# CONNECTOR_B.net
KiCad netlist of a schematic drawn in Altium Designer
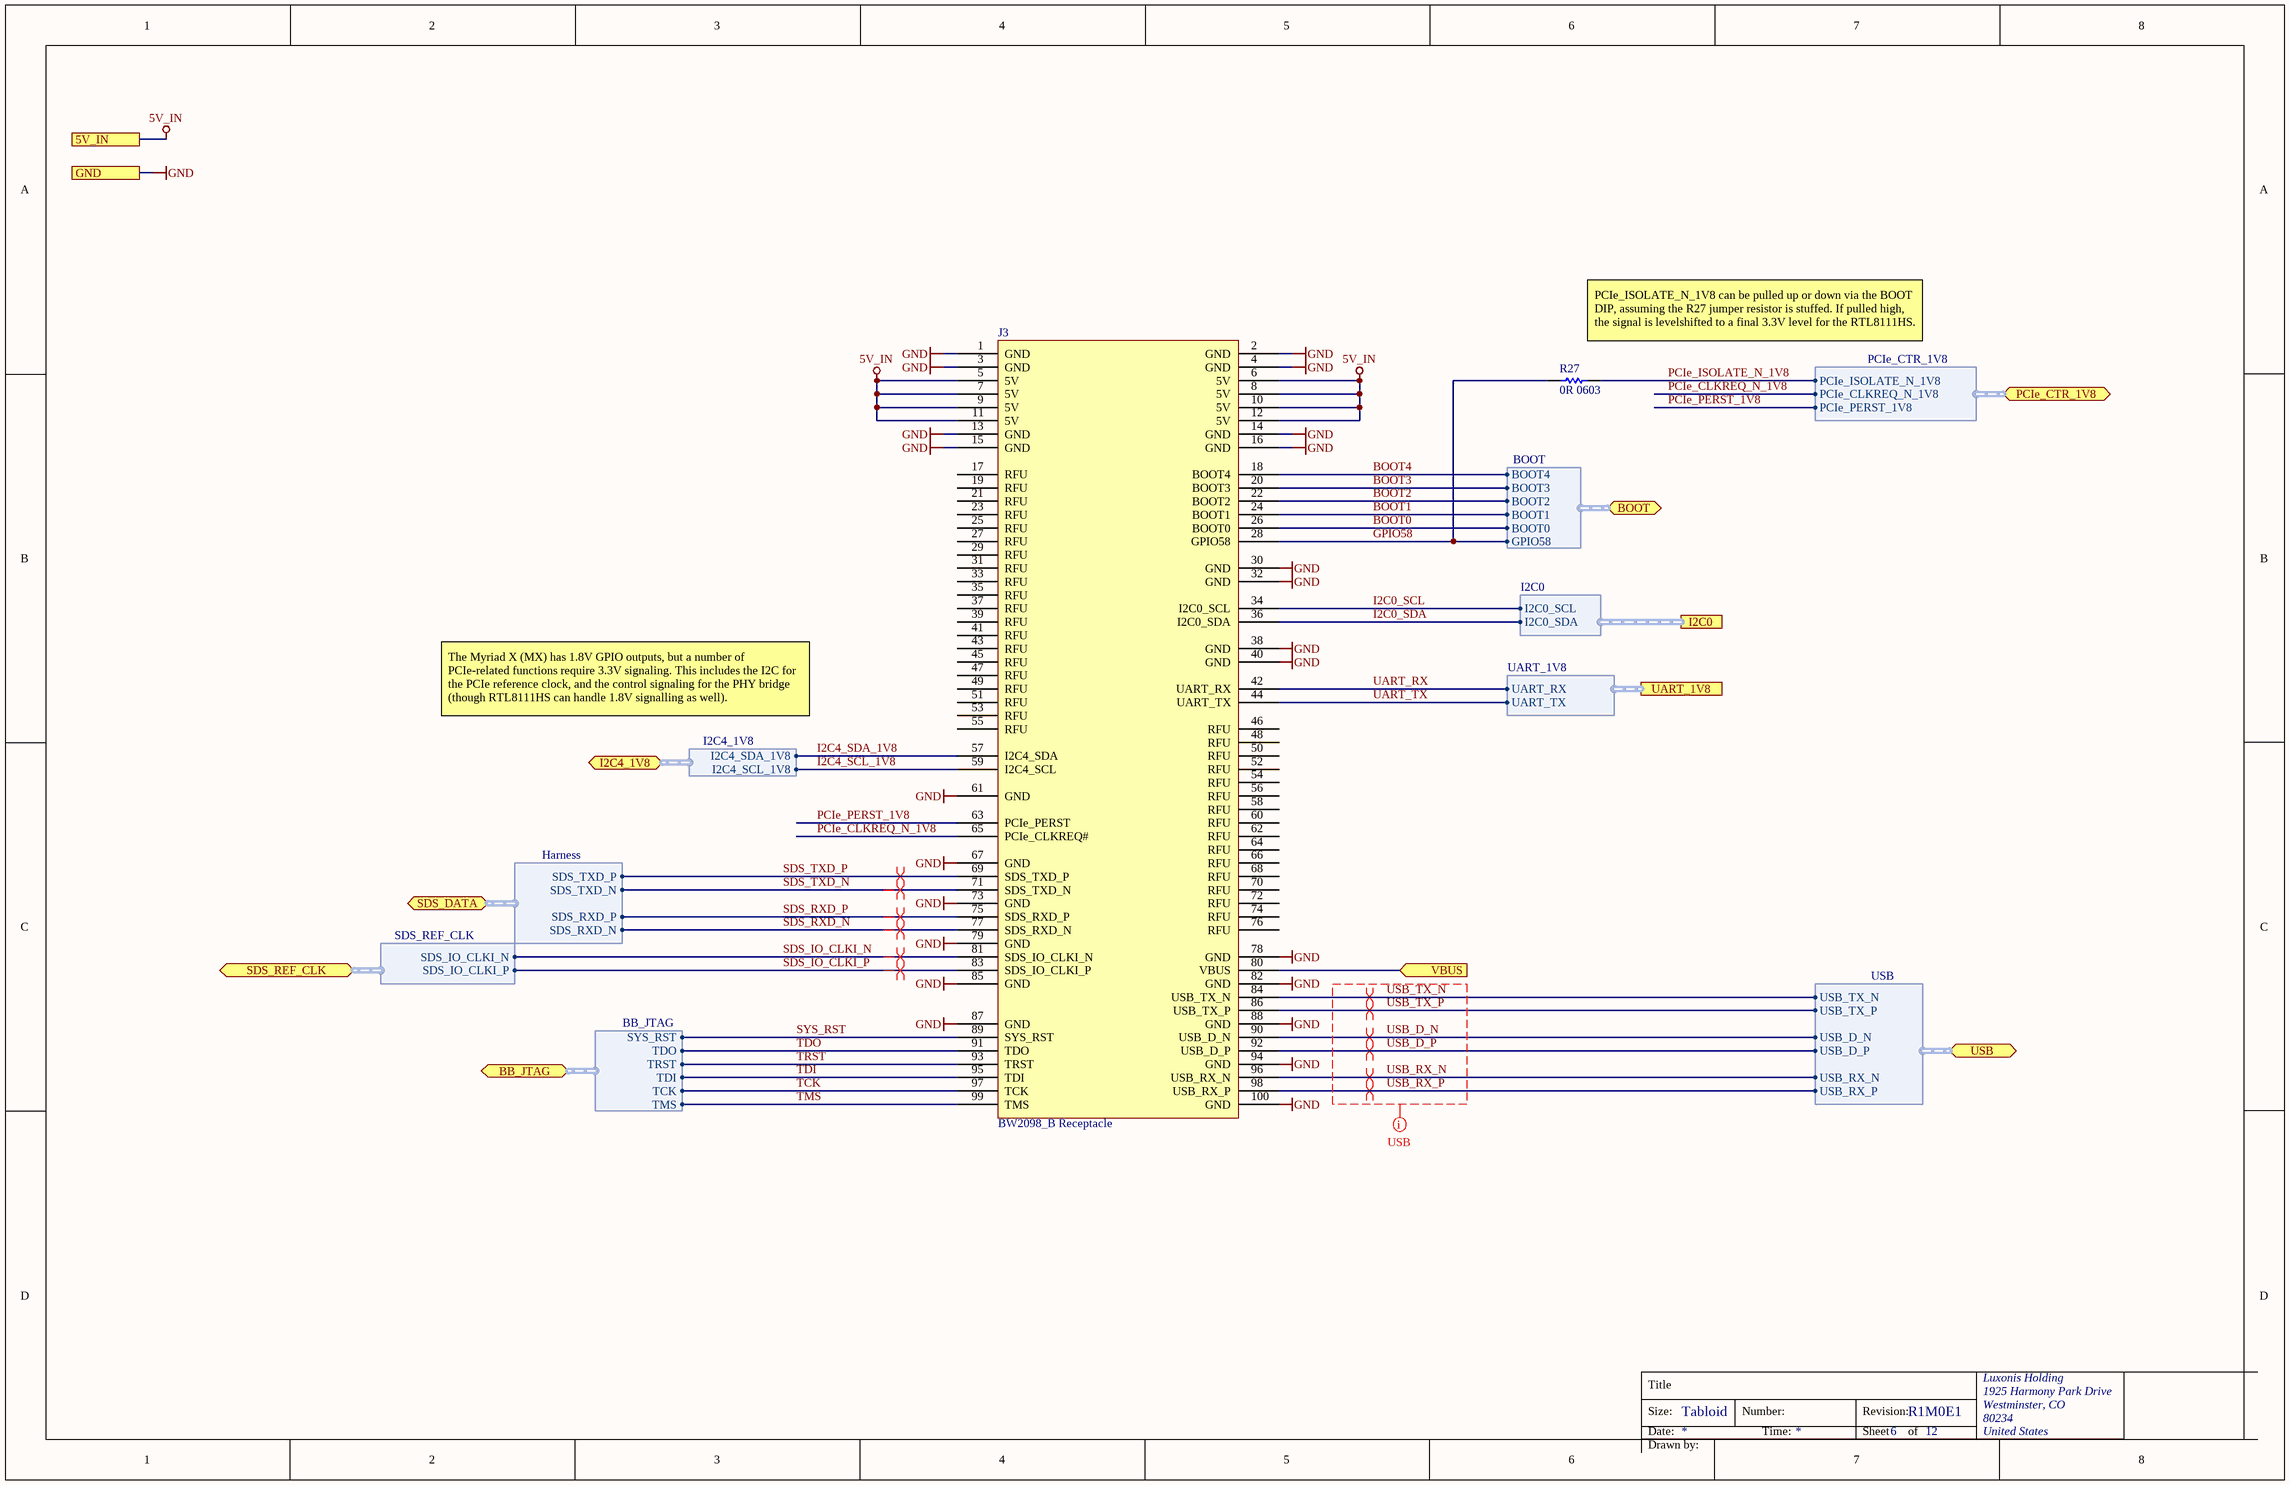
[diagram p0: CONNECTOR_B.SchDoc]

(export (version "E")
  (design (tool "Eeschema 10.0.6"))
  (components
    (comp (ref "J3")
      (value "BW2098_B Receptacle")
      (footprint "LuxonisMaster:DF40HC-3.0-100DS-0.4V_minpad")
      (description "CONN RCPT 100POS 0.4MM SMD GOLD BW2098_B Receptacle")
      (libsource (lib "BW2098POE") (part "DF40HC(3.0)-100DS-0.4V_BW2098_B"))
    )
    (comp (ref "R27")
      (value "0R 0603")
      (footprint "RES_Altium_Vault_Generic:RESC0603(1608)_N")
      (fields (field (name "TOLERANCE") "5%"))
      (libsource (lib "LuxonisMaster") (part "CRCW06030000Z0EA"))
    )
  )
  (nets
    (net (code "10") (name "/BOOT0") (class "Default")
      (node (ref "J3") (pin "26") (pinfunction "BOOT0_26") (pintype "passive"))
    )
    (net (code "11") (name "/BOOT1") (class "Default")
      (node (ref "J3") (pin "24") (pinfunction "BOOT1_24") (pintype "passive"))
    )
    (net (code "12") (name "/BOOT2") (class "Default")
      (node (ref "J3") (pin "22") (pinfunction "BOOT2_22") (pintype "passive"))
    )
    (net (code "13") (name "/BOOT3") (class "Default")
      (node (ref "J3") (pin "20") (pinfunction "BOOT3_20") (pintype "passive"))
    )
    (net (code "14") (name "/BOOT4") (class "Default")
      (node (ref "J3") (pin "18") (pinfunction "BOOT4_18") (pintype "passive"))
    )
    (net (code "15") (name "/GPIO58") (class "Default")
      (node (ref "J3") (pin "28") (pinfunction "GPIO58_28") (pintype "passive"))
      (node (ref "R27") (pin "1") (pinfunction "1_1") (pintype "passive"))
    )
    (net (code "16") (name "/I2C0_SCL") (class "Default")
      (node (ref "J3") (pin "34") (pinfunction "I2C0_SCL_34") (pintype "passive"))
    )
    (net (code "17") (name "/I2C0_SDA") (class "Default")
      (node (ref "J3") (pin "36") (pinfunction "I2C0_SDA_36") (pintype "passive"))
    )
    (net (code "18") (name "/I2C4_SCL_1V8") (class "Default")
      (node (ref "J3") (pin "59") (pinfunction "I2C4_SCL_59") (pintype "passive"))
    )
    (net (code "19") (name "/I2C4_SDA_1V8") (class "Default")
      (node (ref "J3") (pin "57") (pinfunction "I2C4_SDA_57") (pintype "passive"))
    )
    (net (code "20") (name "/PCIe_CLKREQ_N_1V8") (class "Default")
      (node (ref "J3") (pin "65") (pinfunction "PCIe_CLKREQ#_65") (pintype "passive"))
    )
    (net (code "21") (name "/PCIe_ISOLATE_N_1V8") (class "Default")
      (node (ref "R27") (pin "2") (pinfunction "2_2") (pintype "passive"))
    )
    (net (code "22") (name "/PCIe_PERST_1V8") (class "Default")
      (node (ref "J3") (pin "63") (pinfunction "PCIe_PERST_63") (pintype "passive"))
    )
    (net (code "23") (name "/SDS_IO_CLKI_N") (class "Default")
      (node (ref "J3") (pin "81") (pinfunction "SDS_IO_CLKI_N_81") (pintype "passive"))
    )
    (net (code "24") (name "/SDS_IO_CLKI_P") (class "Default")
      (node (ref "J3") (pin "83") (pinfunction "SDS_IO_CLKI_P_83") (pintype "passive"))
    )
    (net (code "25") (name "/SDS_RXD_N") (class "Default")
      (node (ref "J3") (pin "77") (pinfunction "SDS_RXD_N_77") (pintype "passive"))
    )
    (net (code "26") (name "/SDS_RXD_P") (class "Default")
      (node (ref "J3") (pin "75") (pinfunction "SDS_RXD_P_75") (pintype "passive"))
    )
    (net (code "27") (name "/SDS_TXD_N") (class "Default")
      (node (ref "J3") (pin "71") (pinfunction "SDS_TXD_N_71") (pintype "passive"))
    )
    (net (code "28") (name "/SDS_TXD_P") (class "Default")
      (node (ref "J3") (pin "69") (pinfunction "SDS_TXD_P_69") (pintype "passive"))
    )
    (net (code "29") (name "/SYS_RST") (class "Default")
      (node (ref "J3") (pin "89") (pinfunction "SYS_RST_89") (pintype "passive"))
    )
    (net (code "30") (name "/TCK") (class "Default")
      (node (ref "J3") (pin "97") (pinfunction "TCK_97") (pintype "passive"))
    )
    (net (code "31") (name "/TDI") (class "Default")
      (node (ref "J3") (pin "95") (pinfunction "TDI_95") (pintype "passive"))
    )
    (net (code "32") (name "/TDO") (class "Default")
      (node (ref "J3") (pin "91") (pinfunction "TDO_91") (pintype "passive"))
    )
    (net (code "33") (name "/TMS") (class "Default")
      (node (ref "J3") (pin "99") (pinfunction "TMS_99") (pintype "passive"))
    )
    (net (code "34") (name "/TRST") (class "Default")
      (node (ref "J3") (pin "93") (pinfunction "TRST_93") (pintype "passive"))
    )
    (net (code "35") (name "/UART_RX") (class "Default")
      (node (ref "J3") (pin "42") (pinfunction "UART_RX_42") (pintype "passive"))
    )
    (net (code "36") (name "/UART_TX") (class "Default")
      (node (ref "J3") (pin "44") (pinfunction "UART_TX_44") (pintype "passive"))
    )
    (net (code "37") (name "/USB_D_N") (class "Default")
      (node (ref "J3") (pin "90") (pinfunction "USB_D_N_90") (pintype "passive"))
    )
    (net (code "38") (name "/USB_D_P") (class "Default")
      (node (ref "J3") (pin "92") (pinfunction "USB_D_P_92") (pintype "passive"))
    )
    (net (code "39") (name "/USB_RX_N") (class "Default")
      (node (ref "J3") (pin "96") (pinfunction "USB_RX_N_96") (pintype "passive"))
    )
    (net (code "40") (name "/USB_RX_P") (class "Default")
      (node (ref "J3") (pin "98") (pinfunction "USB_RX_P_98") (pintype "passive"))
    )
    (net (code "41") (name "/USB_TX_N") (class "Default")
      (node (ref "J3") (pin "84") (pinfunction "USB_TX_N_84") (pintype "passive"))
    )
    (net (code "42") (name "/USB_TX_P") (class "Default")
      (node (ref "J3") (pin "86") (pinfunction "USB_TX_P_86") (pintype "passive"))
    )
    (net (code "43") (name "/VBUS") (class "Default")
      (node (ref "J3") (pin "80") (pinfunction "VBUS_80") (pintype "passive"))
    )
    (net (code "53") (name "5V_IN") (class "Default")
      (node (ref "J3") (pin "10") (pinfunction "5V_10") (pintype "passive"))
      (node (ref "J3") (pin "11") (pinfunction "5V_11") (pintype "passive"))
      (node (ref "J3") (pin "12") (pinfunction "5V_12") (pintype "passive"))
      (node (ref "J3") (pin "5") (pinfunction "5V_5") (pintype "passive"))
      (node (ref "J3") (pin "6") (pinfunction "5V_6") (pintype "passive"))
      (node (ref "J3") (pin "7") (pinfunction "5V_7") (pintype "passive"))
      (node (ref "J3") (pin "8") (pinfunction "5V_8") (pintype "passive"))
      (node (ref "J3") (pin "9") (pinfunction "5V_9") (pintype "passive"))
    )
    (net (code "54") (name "GND") (class "Default")
      (node (ref "J3") (pin "1") (pinfunction "GND_1") (pintype "passive"))
      (node (ref "J3") (pin "100") (pinfunction "GND_100") (pintype "passive"))
      (node (ref "J3") (pin "13") (pinfunction "GND_13") (pintype "passive"))
      (node (ref "J3") (pin "14") (pinfunction "GND_14") (pintype "passive"))
      (node (ref "J3") (pin "15") (pinfunction "GND_15") (pintype "passive"))
      (node (ref "J3") (pin "16") (pinfunction "GND_16") (pintype "passive"))
      (node (ref "J3") (pin "2") (pinfunction "GND_2") (pintype "passive"))
      (node (ref "J3") (pin "3") (pinfunction "GND_3") (pintype "passive"))
      (node (ref "J3") (pin "30") (pinfunction "GND_30") (pintype "passive"))
      (node (ref "J3") (pin "32") (pinfunction "GND_32") (pintype "passive"))
      (node (ref "J3") (pin "38") (pinfunction "GND_38") (pintype "passive"))
      (node (ref "J3") (pin "4") (pinfunction "GND_4") (pintype "passive"))
      (node (ref "J3") (pin "40") (pinfunction "GND_40") (pintype "passive"))
      (node (ref "J3") (pin "61") (pinfunction "GND_61") (pintype "passive"))
      (node (ref "J3") (pin "67") (pinfunction "GND_67") (pintype "passive"))
      (node (ref "J3") (pin "73") (pinfunction "GND_73") (pintype "passive"))
      (node (ref "J3") (pin "78") (pinfunction "GND_78") (pintype "passive"))
      (node (ref "J3") (pin "79") (pinfunction "GND_79") (pintype "passive"))
      (node (ref "J3") (pin "82") (pinfunction "GND_82") (pintype "passive"))
      (node (ref "J3") (pin "85") (pinfunction "GND_85") (pintype "passive"))
      (node (ref "J3") (pin "87") (pinfunction "GND_87") (pintype "passive"))
      (node (ref "J3") (pin "88") (pinfunction "GND_88") (pintype "passive"))
      (node (ref "J3") (pin "94") (pinfunction "GND_94") (pintype "passive"))
    )
    (net (code "55") (name "unconnected-(J3-RFU-Pad17)") (class "Default")
      (node (ref "J3") (pin "17") (pinfunction "RFU_17") (pintype "passive"))
    )
    (net (code "56") (name "unconnected-(J3-RFU-Pad19)") (class "Default")
      (node (ref "J3") (pin "19") (pinfunction "RFU_19") (pintype "passive"))
    )
    (net (code "57") (name "unconnected-(J3-RFU-Pad21)") (class "Default")
      (node (ref "J3") (pin "21") (pinfunction "RFU_21") (pintype "passive"))
    )
    (net (code "58") (name "unconnected-(J3-RFU-Pad23)") (class "Default")
      (node (ref "J3") (pin "23") (pinfunction "RFU_23") (pintype "passive"))
    )
    (net (code "59") (name "unconnected-(J3-RFU-Pad25)") (class "Default")
      (node (ref "J3") (pin "25") (pinfunction "RFU_25") (pintype "passive"))
    )
    (net (code "60") (name "unconnected-(J3-RFU-Pad27)") (class "Default")
      (node (ref "J3") (pin "27") (pinfunction "RFU_27") (pintype "passive"))
    )
    (net (code "61") (name "unconnected-(J3-RFU-Pad29)") (class "Default")
      (node (ref "J3") (pin "29") (pinfunction "RFU_29") (pintype "passive"))
    )
    (net (code "62") (name "unconnected-(J3-RFU-Pad31)") (class "Default")
      (node (ref "J3") (pin "31") (pinfunction "RFU_31") (pintype "passive"))
    )
    (net (code "63") (name "unconnected-(J3-RFU-Pad33)") (class "Default")
      (node (ref "J3") (pin "33") (pinfunction "RFU_33") (pintype "passive"))
    )
    (net (code "64") (name "unconnected-(J3-RFU-Pad35)") (class "Default")
      (node (ref "J3") (pin "35") (pinfunction "RFU_35") (pintype "passive"))
    )
    (net (code "65") (name "unconnected-(J3-RFU-Pad37)") (class "Default")
      (node (ref "J3") (pin "37") (pinfunction "RFU_37") (pintype "passive"))
    )
    (net (code "66") (name "unconnected-(J3-RFU-Pad39)") (class "Default")
      (node (ref "J3") (pin "39") (pinfunction "RFU_39") (pintype "passive"))
    )
    (net (code "67") (name "unconnected-(J3-RFU-Pad41)") (class "Default")
      (node (ref "J3") (pin "41") (pinfunction "RFU_41") (pintype "passive"))
    )
    (net (code "68") (name "unconnected-(J3-RFU-Pad43)") (class "Default")
      (node (ref "J3") (pin "43") (pinfunction "RFU_43") (pintype "passive"))
    )
    (net (code "69") (name "unconnected-(J3-RFU-Pad45)") (class "Default")
      (node (ref "J3") (pin "45") (pinfunction "RFU_45") (pintype "passive"))
    )
    (net (code "70") (name "unconnected-(J3-RFU-Pad46)") (class "Default")
      (node (ref "J3") (pin "46") (pinfunction "RFU_46") (pintype "passive"))
    )
    (net (code "71") (name "unconnected-(J3-RFU-Pad47)") (class "Default")
      (node (ref "J3") (pin "47") (pinfunction "RFU_47") (pintype "passive"))
    )
    (net (code "72") (name "unconnected-(J3-RFU-Pad48)") (class "Default")
      (node (ref "J3") (pin "48") (pinfunction "RFU_48") (pintype "passive"))
    )
    (net (code "73") (name "unconnected-(J3-RFU-Pad49)") (class "Default")
      (node (ref "J3") (pin "49") (pinfunction "RFU_49") (pintype "passive"))
    )
    (net (code "74") (name "unconnected-(J3-RFU-Pad50)") (class "Default")
      (node (ref "J3") (pin "50") (pinfunction "RFU_50") (pintype "passive"))
    )
    (net (code "75") (name "unconnected-(J3-RFU-Pad51)") (class "Default")
      (node (ref "J3") (pin "51") (pinfunction "RFU_51") (pintype "passive"))
    )
    (net (code "76") (name "unconnected-(J3-RFU-Pad52)") (class "Default")
      (node (ref "J3") (pin "52") (pinfunction "RFU_52") (pintype "passive"))
    )
    (net (code "77") (name "unconnected-(J3-RFU-Pad53)") (class "Default")
      (node (ref "J3") (pin "53") (pinfunction "RFU_53") (pintype "passive"))
    )
    (net (code "78") (name "unconnected-(J3-RFU-Pad54)") (class "Default")
      (node (ref "J3") (pin "54") (pinfunction "RFU_54") (pintype "passive"))
    )
    (net (code "79") (name "unconnected-(J3-RFU-Pad55)") (class "Default")
      (node (ref "J3") (pin "55") (pinfunction "RFU_55") (pintype "passive"))
    )
    (net (code "80") (name "unconnected-(J3-RFU-Pad56)") (class "Default")
      (node (ref "J3") (pin "56") (pinfunction "RFU_56") (pintype "passive"))
    )
    (net (code "81") (name "unconnected-(J3-RFU-Pad58)") (class "Default")
      (node (ref "J3") (pin "58") (pinfunction "RFU_58") (pintype "passive"))
    )
    (net (code "82") (name "unconnected-(J3-RFU-Pad60)") (class "Default")
      (node (ref "J3") (pin "60") (pinfunction "RFU_60") (pintype "passive"))
    )
    (net (code "83") (name "unconnected-(J3-RFU-Pad62)") (class "Default")
      (node (ref "J3") (pin "62") (pinfunction "RFU_62") (pintype "passive"))
    )
    (net (code "84") (name "unconnected-(J3-RFU-Pad64)") (class "Default")
      (node (ref "J3") (pin "64") (pinfunction "RFU_64") (pintype "passive"))
    )
    (net (code "85") (name "unconnected-(J3-RFU-Pad66)") (class "Default")
      (node (ref "J3") (pin "66") (pinfunction "RFU_66") (pintype "passive"))
    )
    (net (code "86") (name "unconnected-(J3-RFU-Pad68)") (class "Default")
      (node (ref "J3") (pin "68") (pinfunction "RFU_68") (pintype "passive"))
    )
    (net (code "87") (name "unconnected-(J3-RFU-Pad70)") (class "Default")
      (node (ref "J3") (pin "70") (pinfunction "RFU_70") (pintype "passive"))
    )
    (net (code "88") (name "unconnected-(J3-RFU-Pad72)") (class "Default")
      (node (ref "J3") (pin "72") (pinfunction "RFU_72") (pintype "passive"))
    )
    (net (code "89") (name "unconnected-(J3-RFU-Pad74)") (class "Default")
      (node (ref "J3") (pin "74") (pinfunction "RFU_74") (pintype "passive"))
    )
    (net (code "90") (name "unconnected-(J3-RFU-Pad76)") (class "Default")
      (node (ref "J3") (pin "76") (pinfunction "RFU_76") (pintype "passive"))
    )
  )
)
